# Soil_EH_Comparator.net
KiCad netlist of a schematic drawn in Altium Designer
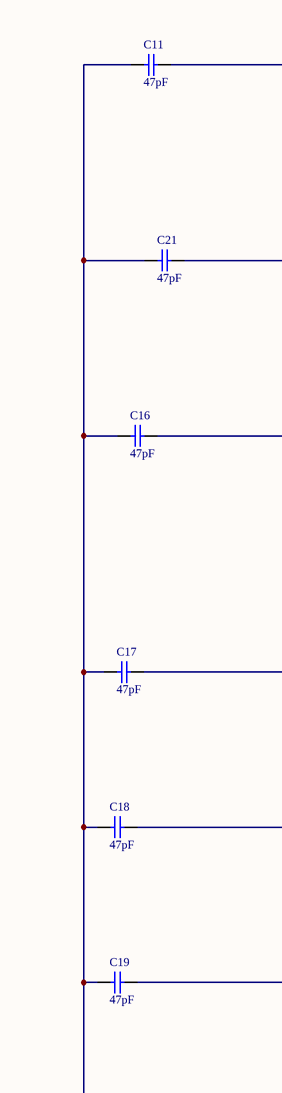
[diagram p0: Soil_EH_Comparator.SchDoc, top left]
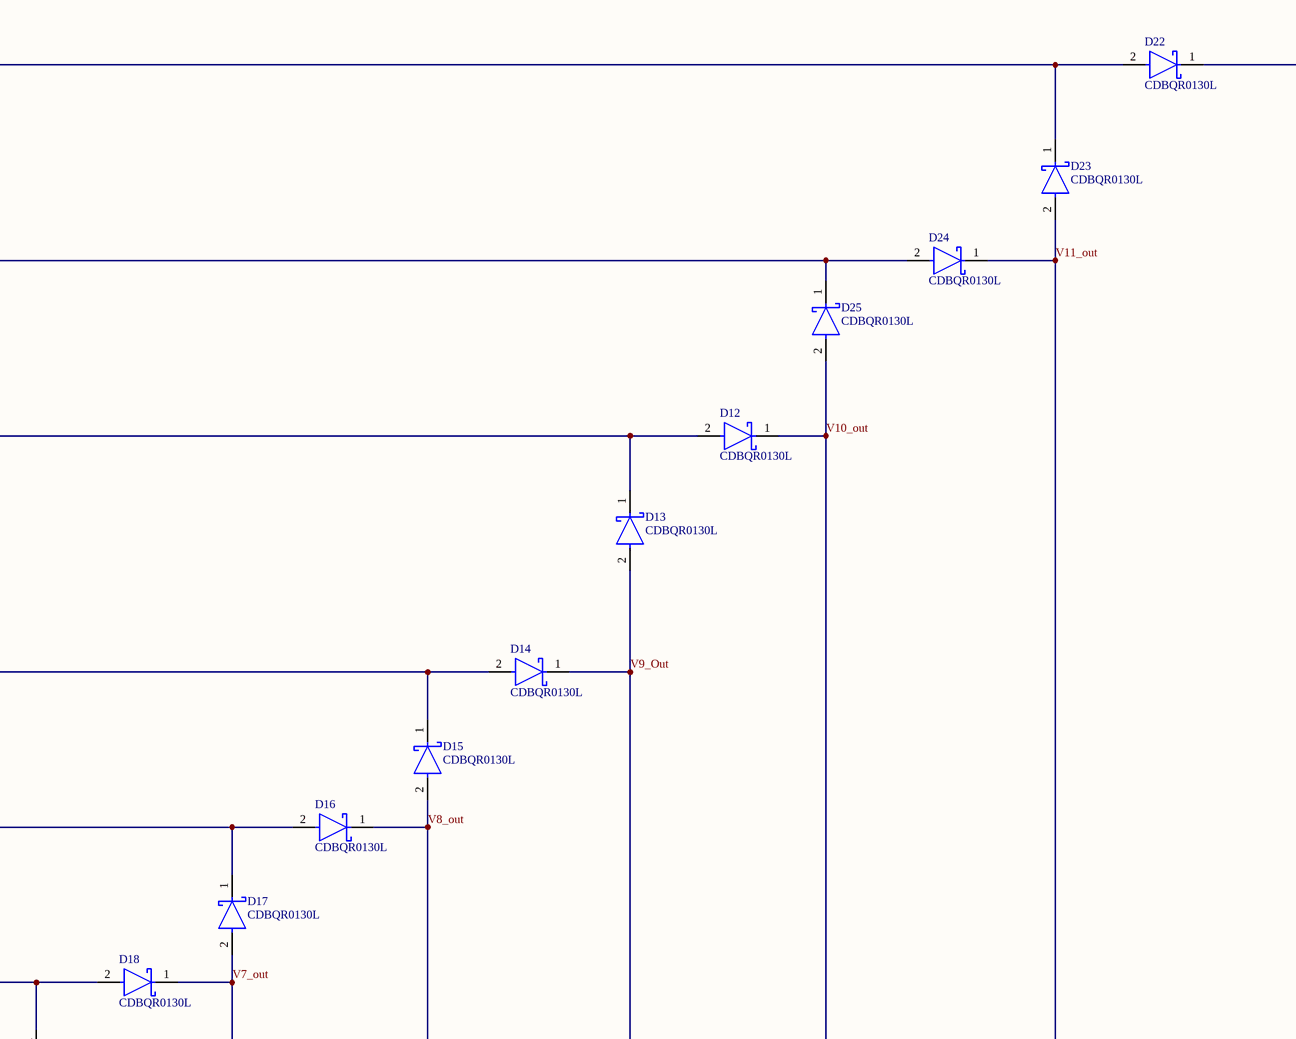
[diagram p1: Soil_EH_Comparator.SchDoc, top middle]
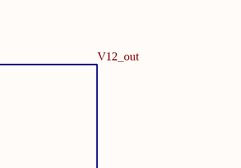
[diagram p2: Soil_EH_Comparator.SchDoc, top right]
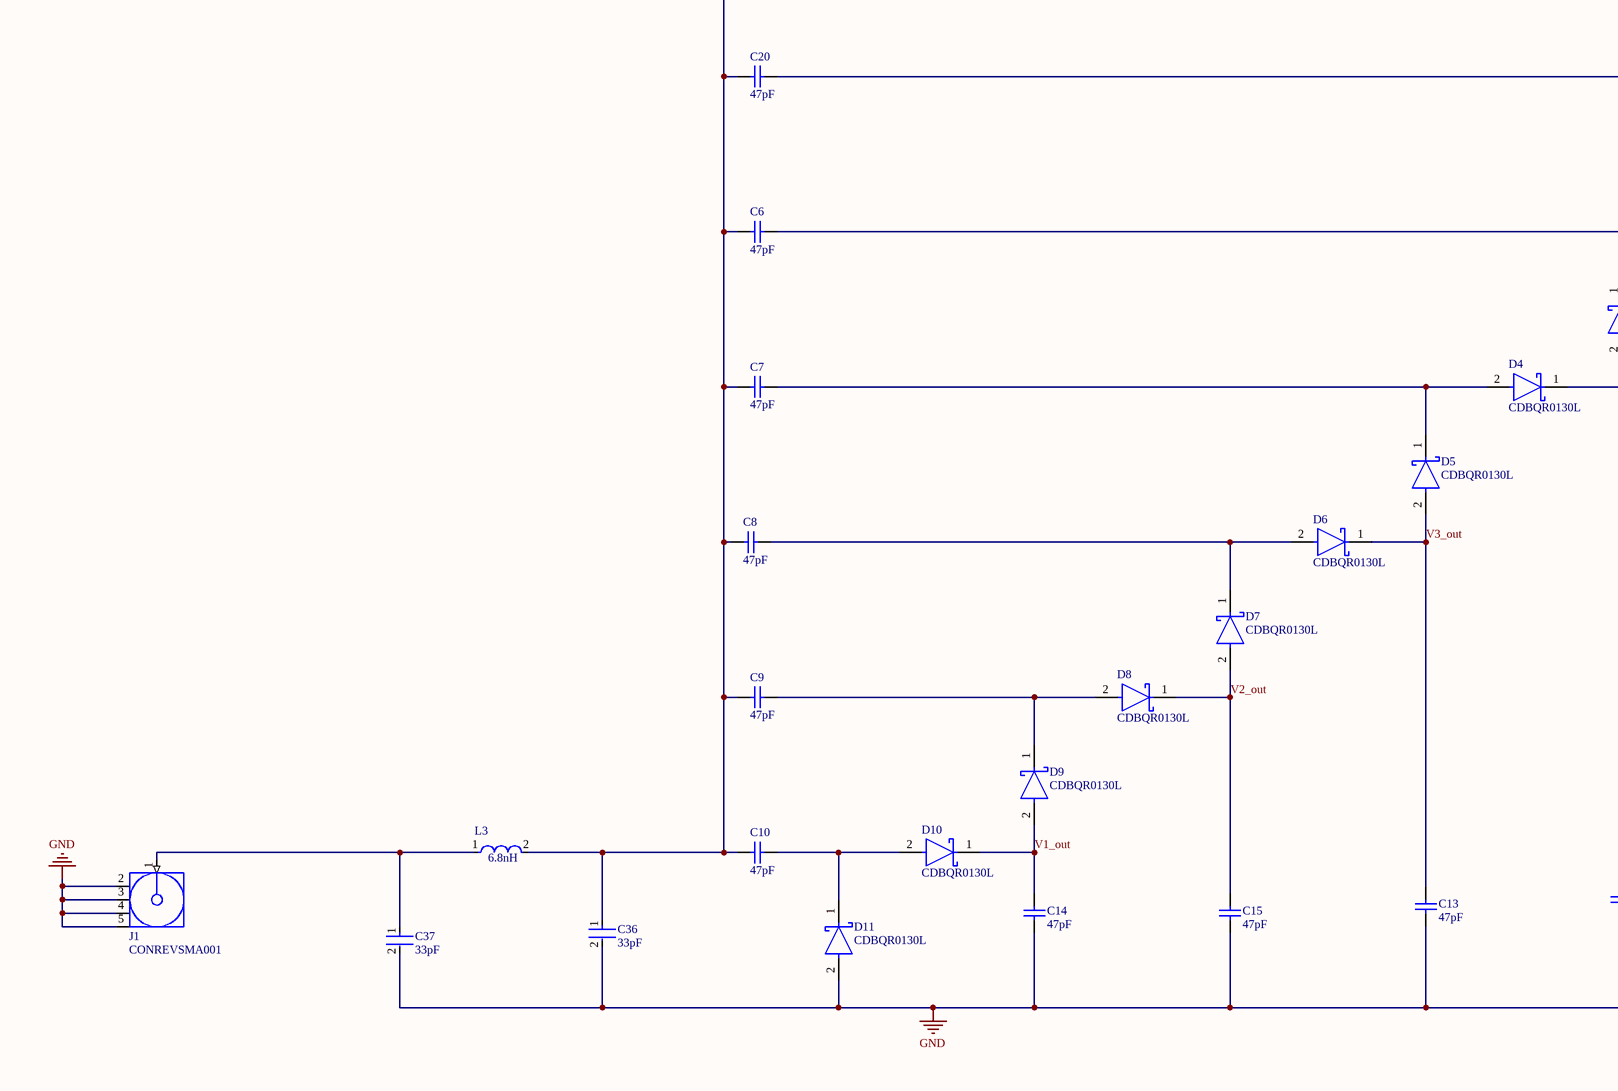
[diagram p3: Soil_EH_Comparator.SchDoc, bottom left]
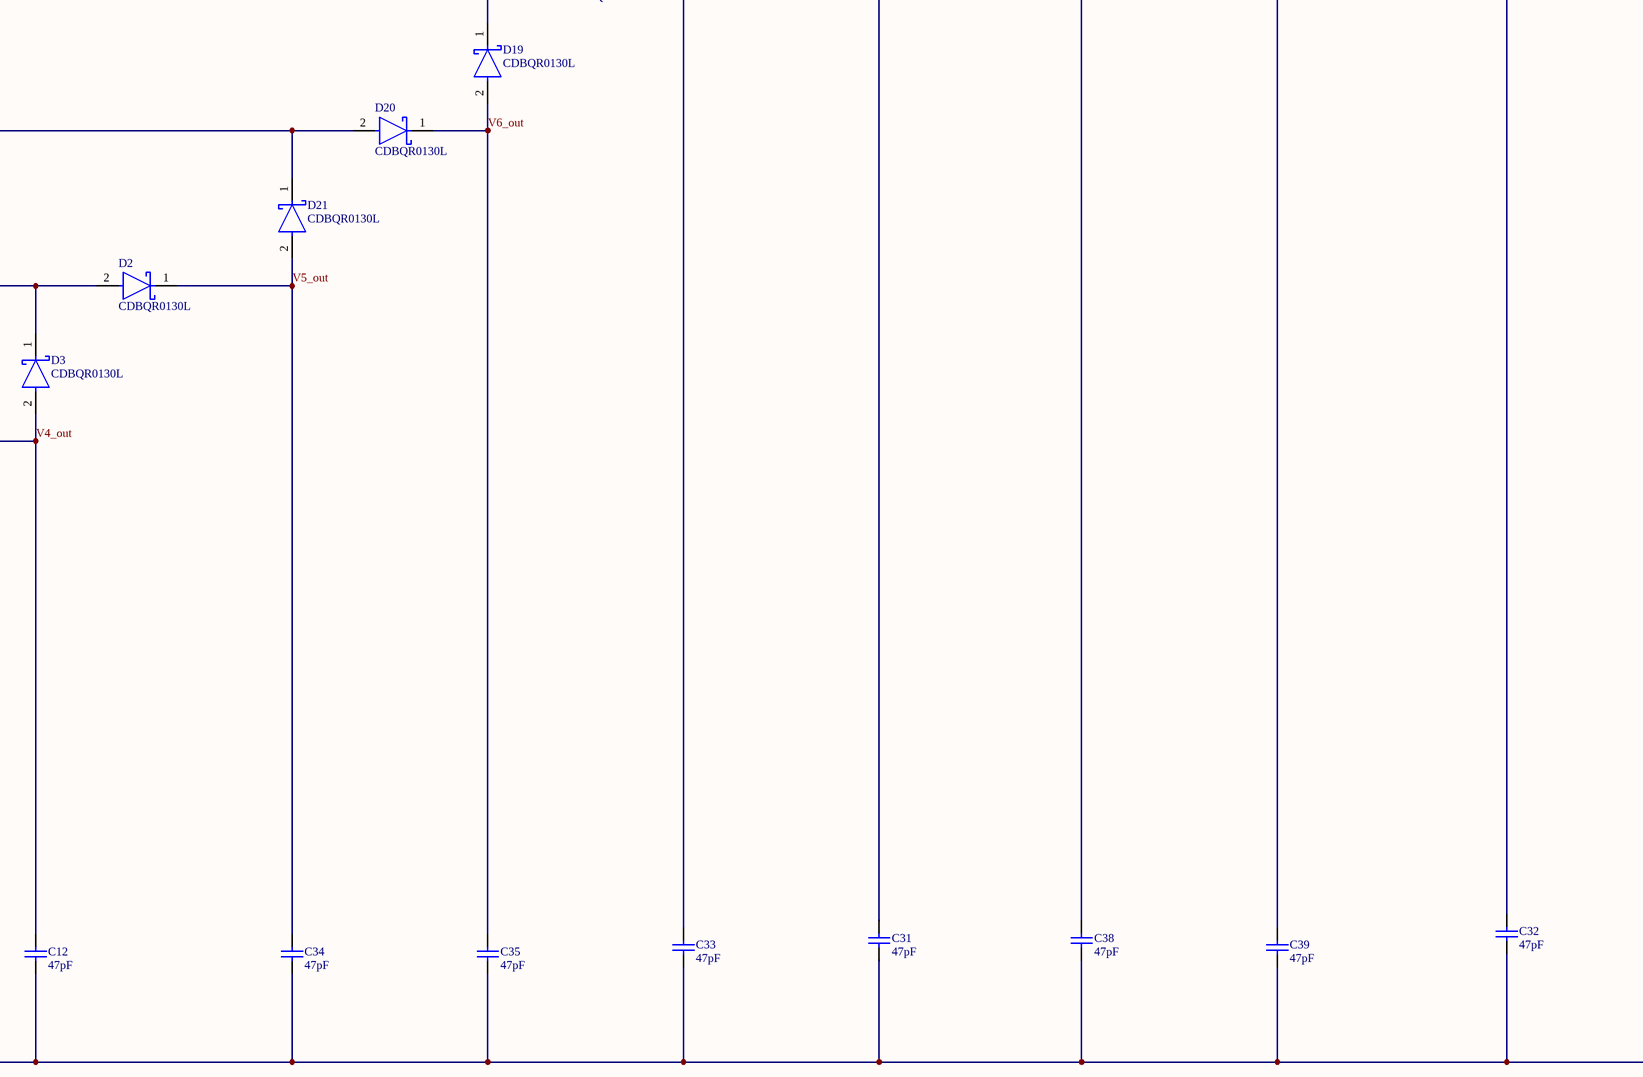
[diagram p4: Soil_EH_Comparator.SchDoc, bottom middle]
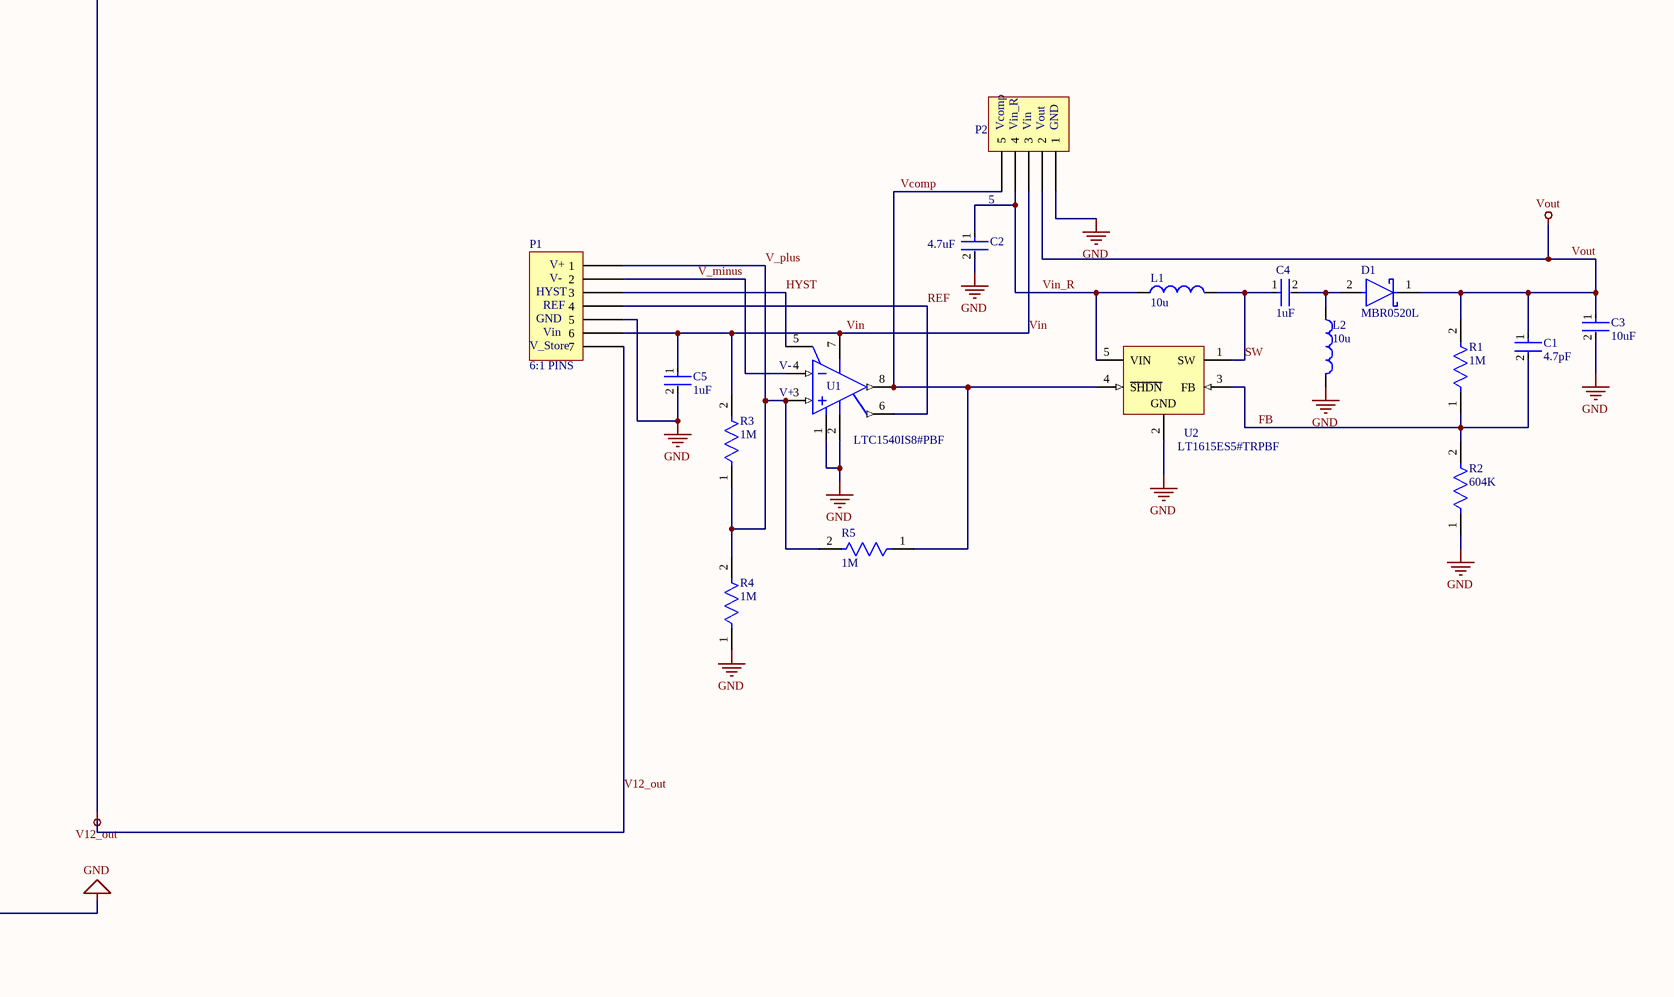
[diagram p5: Soil_EH_Comparator.SchDoc, bottom right]

(export (version "E")
  (design (tool "Eeschema 10.0.6"))
  (components
    (comp (ref "C1")
      (value "4.7pF")
      (footprint "FP-C0603C-CF-MFG")
      (description "CAP CER 4.7PF 25V C0G/NP0 0603")
      (fields
        (field (name "OCTOPART") "https://octopart.com/c0603c479c3gacauto-kemet-21768564")
        (field (name "MANUFACTURER PART NUMBER") "C0603C479C3GACAUTO")
      )
      (libsource (lib "Altium Content Vault") (part "b4654b650e69147ec39a6b967a45e02"))
    )
    (comp (ref "C2")
      (value "4.7uF")
      (footprint "FP-GRM188-0_15-IPC_C")
      (description "Chip Multilayer Ceramic Capacitors for General Purpose, 0603, 4.7uF, X5R, 15%, 10%, 25V")
      (fields (field (name "VOLTAGE") "25V") (field (name "TOLERANCE") "10%"))
      (libsource (lib "Altium Content Vault") (part "02cd4be3c70576c341d710602a673aa"))
    )
    (comp (ref "C3")
      (value "10uF")
      (footprint "FP-GRM21B-0_1-MFG")
      (description "Chip Multilayer Ceramic Capacitors for General Purpose, 0805, 10uF, X5R, 15%, 10%, 16V")
      (fields (field (name "TOLERANCE") "10%") (field (name "VOLTAGE") "16V"))
      (libsource (lib "Altium Content Vault") (part "b4654b650e69147ec39a6b967a45e02"))
    )
    (comp (ref "C4")
      (value "1uF")
      (footprint "FP-0603-L_1_6_0_1-W_0_8_0-IPC_C")
      (description "None")
      (fields (field (name "TOLERANCE") "10%"))
      (libsource (lib "Altium Content Vault") (part "02cd4be3c70576c341d710602a673aa"))
    )
    (comp (ref "C5")
      (value "1uF")
      (footprint "FP-0603-L_1_6_0_1-W_0_8_0-IPC_C")
      (description "None")
      (fields (field (name "TOLERANCE") "10%"))
      (libsource (lib "Altium Content Vault") (part "02cd4be3c70576c341d710602a673aa"))
    )
    (comp (ref "C6")
      (value "47pF")
      (footprint "CAPC1608X95X40LL15T15")
      (fields (field (name "PART NUMBER") "VJ0603A470FXACW1BC") (field (name "MANUFACTURER") "Vitramon"))
      (libsource (lib "Altium Content Vault") (part "CAP"))
    )
    (comp (ref "C7")
      (value "47pF")
      (footprint "CAPC1608X95X40LL15T15")
      (fields (field (name "PART NUMBER") "VJ0603A470FXACW1BC") (field (name "MANUFACTURER") "Vitramon"))
      (libsource (lib "Altium Content Vault") (part "CAP"))
    )
    (comp (ref "C8")
      (value "47pF")
      (footprint "CAPC1608X95X40LL15T15")
      (fields (field (name "PART NUMBER") "VJ0603A470FXACW1BC") (field (name "MANUFACTURER") "Vitramon"))
      (libsource (lib "Altium Content Vault") (part "CAP"))
    )
    (comp (ref "C9")
      (value "47pF")
      (footprint "CAPC1608X95X40LL15T15")
      (fields (field (name "PART NUMBER") "VJ0603A470FXACW1BC") (field (name "MANUFACTURER") "Vitramon"))
      (libsource (lib "Altium Content Vault") (part "CAP"))
    )
    (comp (ref "C10")
      (value "47pF")
      (footprint "CAPC1608X95X40LL15T15")
      (fields (field (name "PART NUMBER") "VJ0603A470FXACW1BC") (field (name "MANUFACTURER") "Vitramon"))
      (libsource (lib "Altium Content Vault") (part "CAP"))
    )
    (comp (ref "C11")
      (value "47pF")
      (footprint "CAPC1608X95X40LL15T15")
      (fields (field (name "PART NUMBER") "VJ0603A470FXACW1BC") (field (name "MANUFACTURER") "Vitramon"))
      (libsource (lib "Altium Content Vault") (part "CAP"))
    )
    (comp (ref "C12")
      (value "47pF")
      (footprint "CAPC1608X95X40LL15T15")
      (fields (field (name "PART NUMBER") "VJ0603A470FXACW1BC") (field (name "MANUFACTURER") "Vitramon"))
      (libsource (lib "Altium Content Vault") (part "CAP"))
    )
    (comp (ref "C13")
      (value "47pF")
      (footprint "CAPC1608X95X40LL15T15")
      (fields (field (name "PART NUMBER") "VJ0603A470FXACW1BC") (field (name "MANUFACTURER") "Vitramon"))
      (libsource (lib "Altium Content Vault") (part "CAP"))
    )
    (comp (ref "C14")
      (value "47pF")
      (footprint "CAPC1608X95X40LL15T15")
      (fields (field (name "PART NUMBER") "VJ0603A470FXACW1BC") (field (name "MANUFACTURER") "Vitramon"))
      (libsource (lib "Altium Content Vault") (part "CAP"))
    )
    (comp (ref "C15")
      (value "47pF")
      (footprint "CAPC1608X95X40LL15T15")
      (fields (field (name "PART NUMBER") "VJ0603A470FXACW1BC") (field (name "MANUFACTURER") "Vitramon"))
      (libsource (lib "Altium Content Vault") (part "CAP"))
    )
    (comp (ref "C16")
      (value "47pF")
      (footprint "CAPC1608X95X40LL15T15")
      (fields (field (name "PART NUMBER") "VJ0603A470FXACW1BC") (field (name "MANUFACTURER") "Vitramon"))
      (libsource (lib "Altium Content Vault") (part "CAP"))
    )
    (comp (ref "C17")
      (value "47pF")
      (footprint "CAPC1608X95X40LL15T15")
      (fields (field (name "PART NUMBER") "VJ0603A470FXACW1BC") (field (name "MANUFACTURER") "Vitramon"))
      (libsource (lib "Altium Content Vault") (part "CAP"))
    )
    (comp (ref "C18")
      (value "47pF")
      (footprint "CAPC1608X95X40LL15T15")
      (fields (field (name "PART NUMBER") "VJ0603A470FXACW1BC") (field (name "MANUFACTURER") "Vitramon"))
      (libsource (lib "Altium Content Vault") (part "CAP"))
    )
    (comp (ref "C19")
      (value "47pF")
      (footprint "CAPC1608X95X40LL15T15")
      (fields (field (name "PART NUMBER") "VJ0603A470FXACW1BC") (field (name "MANUFACTURER") "Vitramon"))
      (libsource (lib "Altium Content Vault") (part "CAP"))
    )
    (comp (ref "C20")
      (value "47pF")
      (footprint "CAPC1608X95X40LL15T15")
      (fields (field (name "PART NUMBER") "VJ0603A470FXACW1BC") (field (name "MANUFACTURER") "Vitramon"))
      (libsource (lib "Altium Content Vault") (part "CAP"))
    )
    (comp (ref "C21")
      (value "47pF")
      (footprint "CAPC1608X95X40LL15T15")
      (fields (field (name "PART NUMBER") "VJ0603A470FXACW1BC") (field (name "MANUFACTURER") "Vitramon"))
      (libsource (lib "Altium Content Vault") (part "CAP"))
    )
    (comp (ref "C31")
      (value "47pF")
      (footprint "CAPC1608X95X40LL15T15")
      (fields (field (name "PART NUMBER") "VJ0603A470FXACW1BC") (field (name "MANUFACTURER") "Vitramon"))
      (libsource (lib "Altium Content Vault") (part "CAP"))
    )
    (comp (ref "C32")
      (value "47pF")
      (footprint "CAPC1608X95X40LL15T15")
      (fields (field (name "PART NUMBER") "VJ0603A470FXACW1BC") (field (name "MANUFACTURER") "Vitramon"))
      (libsource (lib "Altium Content Vault") (part "CAP"))
    )
    (comp (ref "C33")
      (value "47pF")
      (footprint "CAPC1608X95X40LL15T15")
      (fields (field (name "PART NUMBER") "VJ0603A470FXACW1BC") (field (name "MANUFACTURER") "Vitramon"))
      (libsource (lib "Altium Content Vault") (part "CAP"))
    )
    (comp (ref "C34")
      (value "47pF")
      (footprint "CAPC1608X95X40LL15T15")
      (fields (field (name "PART NUMBER") "VJ0603A470FXACW1BC") (field (name "MANUFACTURER") "Vitramon"))
      (libsource (lib "Altium Content Vault") (part "CAP"))
    )
    (comp (ref "C35")
      (value "47pF")
      (footprint "CAPC1608X95X40LL15T15")
      (fields (field (name "PART NUMBER") "VJ0603A470FXACW1BC") (field (name "MANUFACTURER") "Vitramon"))
      (libsource (lib "Altium Content Vault") (part "CAP"))
    )
    (comp (ref "C36")
      (value "33pF")
      (footprint "FP-C0603C-CF-MFG")
      (description "CAP CER 33PF 50V 1% NP0 0603")
      (fields
        (field (name "OCTOPART") "https://octopart.com/c0603c330f5gactu-kemet-9143758")
        (field (name "TOLERANCE") "0.01")
      )
      (libsource (lib "Altium Content Vault") (part "b4654b650e69147ec39a6b967a45e02"))
    )
    (comp (ref "C37")
      (value "33pF")
      (footprint "FP-C0603C-CF-MFG")
      (description "CAP CER 33PF 50V 1% NP0 0603")
      (fields
        (field (name "OCTOPART") "https://octopart.com/c0603c330f5gactu-kemet-9143758")
        (field (name "TOLERANCE") "0.01")
      )
      (libsource (lib "Altium Content Vault") (part "b4654b650e69147ec39a6b967a45e02"))
    )
    (comp (ref "C38")
      (value "47pF")
      (footprint "CAPC1608X95X40LL15T15")
      (fields (field (name "PART NUMBER") "VJ0603A470FXACW1BC") (field (name "MANUFACTURER") "Vitramon"))
      (libsource (lib "Altium Content Vault") (part "CAP"))
    )
    (comp (ref "C39")
      (value "47pF")
      (footprint "CAPC1608X95X40LL15T15")
      (fields (field (name "PART NUMBER") "VJ0603A470FXACW1BC") (field (name "MANUFACTURER") "Vitramon"))
      (libsource (lib "Altium Content Vault") (part "CAP"))
    )
    (comp (ref "D1")
      (value "MBR0520L")
      (footprint "FP-MA02A-MFG")
      (description "DIODE SCHOTTKY 20V 500MA SOD123")
      (libsource (lib "Altium Content Vault") (part "1d6ec82d83fb6aee721767c19dac4b9"))
    )
    (comp (ref "D2")
      (value "CDBQR0130L")
      (footprint "FP-0402-SOD-923F-MFG")
      (description "DIODE SCHOTTKY 30V 100MA 0402")
      (libsource (lib "Altium Content Vault") (part "1d6ec82d83fb6aee721767c19dac4b9"))
    )
    (comp (ref "D3")
      (value "CDBQR0130L")
      (footprint "FP-0402-SOD-923F-MFG")
      (description "DIODE SCHOTTKY 30V 100MA 0402")
      (libsource (lib "Altium Content Vault") (part "1d6ec82d83fb6aee721767c19dac4b9"))
    )
    (comp (ref "D4")
      (value "CDBQR0130L")
      (footprint "FP-0402-SOD-923F-MFG")
      (description "DIODE SCHOTTKY 30V 100MA 0402")
      (libsource (lib "Altium Content Vault") (part "1d6ec82d83fb6aee721767c19dac4b9"))
    )
    (comp (ref "D5")
      (value "CDBQR0130L")
      (footprint "FP-0402-SOD-923F-MFG")
      (description "DIODE SCHOTTKY 30V 100MA 0402")
      (libsource (lib "Altium Content Vault") (part "1d6ec82d83fb6aee721767c19dac4b9"))
    )
    (comp (ref "D6")
      (value "CDBQR0130L")
      (footprint "FP-0402-SOD-923F-MFG")
      (description "DIODE SCHOTTKY 30V 100MA 0402")
      (libsource (lib "Altium Content Vault") (part "1d6ec82d83fb6aee721767c19dac4b9"))
    )
    (comp (ref "D7")
      (value "CDBQR0130L")
      (footprint "FP-0402-SOD-923F-MFG")
      (description "DIODE SCHOTTKY 30V 100MA 0402")
      (libsource (lib "Altium Content Vault") (part "1d6ec82d83fb6aee721767c19dac4b9"))
    )
    (comp (ref "D8")
      (value "CDBQR0130L")
      (footprint "FP-0402-SOD-923F-MFG")
      (description "DIODE SCHOTTKY 30V 100MA 0402")
      (libsource (lib "Altium Content Vault") (part "1d6ec82d83fb6aee721767c19dac4b9"))
    )
    (comp (ref "D9")
      (value "CDBQR0130L")
      (footprint "FP-0402-SOD-923F-MFG")
      (description "DIODE SCHOTTKY 30V 100MA 0402")
      (libsource (lib "Altium Content Vault") (part "1d6ec82d83fb6aee721767c19dac4b9"))
    )
    (comp (ref "D10")
      (value "CDBQR0130L")
      (footprint "FP-0402-SOD-923F-MFG")
      (description "DIODE SCHOTTKY 30V 100MA 0402")
      (libsource (lib "Altium Content Vault") (part "1d6ec82d83fb6aee721767c19dac4b9"))
    )
    (comp (ref "D11")
      (value "CDBQR0130L")
      (footprint "FP-0402-SOD-923F-MFG")
      (description "DIODE SCHOTTKY 30V 100MA 0402")
      (libsource (lib "Altium Content Vault") (part "1d6ec82d83fb6aee721767c19dac4b9"))
    )
    (comp (ref "D12")
      (value "CDBQR0130L")
      (footprint "FP-0402-SOD-923F-MFG")
      (description "DIODE SCHOTTKY 30V 100MA 0402")
      (libsource (lib "Altium Content Vault") (part "1d6ec82d83fb6aee721767c19dac4b9"))
    )
    (comp (ref "D13")
      (value "CDBQR0130L")
      (footprint "FP-0402-SOD-923F-MFG")
      (description "DIODE SCHOTTKY 30V 100MA 0402")
      (libsource (lib "Altium Content Vault") (part "1d6ec82d83fb6aee721767c19dac4b9"))
    )
    (comp (ref "D14")
      (value "CDBQR0130L")
      (footprint "FP-0402-SOD-923F-MFG")
      (description "DIODE SCHOTTKY 30V 100MA 0402")
      (libsource (lib "Altium Content Vault") (part "1d6ec82d83fb6aee721767c19dac4b9"))
    )
    (comp (ref "D15")
      (value "CDBQR0130L")
      (footprint "FP-0402-SOD-923F-MFG")
      (description "DIODE SCHOTTKY 30V 100MA 0402")
      (libsource (lib "Altium Content Vault") (part "1d6ec82d83fb6aee721767c19dac4b9"))
    )
    (comp (ref "D16")
      (value "CDBQR0130L")
      (footprint "FP-0402-SOD-923F-MFG")
      (description "DIODE SCHOTTKY 30V 100MA 0402")
      (libsource (lib "Altium Content Vault") (part "1d6ec82d83fb6aee721767c19dac4b9"))
    )
    (comp (ref "D17")
      (value "CDBQR0130L")
      (footprint "FP-0402-SOD-923F-MFG")
      (description "DIODE SCHOTTKY 30V 100MA 0402")
      (libsource (lib "Altium Content Vault") (part "1d6ec82d83fb6aee721767c19dac4b9"))
    )
    (comp (ref "D18")
      (value "CDBQR0130L")
      (footprint "FP-0402-SOD-923F-MFG")
      (description "DIODE SCHOTTKY 30V 100MA 0402")
      (libsource (lib "Altium Content Vault") (part "1d6ec82d83fb6aee721767c19dac4b9"))
    )
    (comp (ref "D19")
      (value "CDBQR0130L")
      (footprint "FP-0402-SOD-923F-MFG")
      (description "DIODE SCHOTTKY 30V 100MA 0402")
      (libsource (lib "Altium Content Vault") (part "1d6ec82d83fb6aee721767c19dac4b9"))
    )
    (comp (ref "D20")
      (value "CDBQR0130L")
      (footprint "FP-0402-SOD-923F-MFG")
      (description "DIODE SCHOTTKY 30V 100MA 0402")
      (libsource (lib "Altium Content Vault") (part "1d6ec82d83fb6aee721767c19dac4b9"))
    )
    (comp (ref "D21")
      (value "CDBQR0130L")
      (footprint "FP-0402-SOD-923F-MFG")
      (description "DIODE SCHOTTKY 30V 100MA 0402")
      (libsource (lib "Altium Content Vault") (part "1d6ec82d83fb6aee721767c19dac4b9"))
    )
    (comp (ref "D22")
      (value "CDBQR0130L")
      (footprint "FP-0402-SOD-923F-MFG")
      (description "DIODE SCHOTTKY 30V 100MA 0402")
      (libsource (lib "Altium Content Vault") (part "1d6ec82d83fb6aee721767c19dac4b9"))
    )
    (comp (ref "D23")
      (value "CDBQR0130L")
      (footprint "FP-0402-SOD-923F-MFG")
      (description "DIODE SCHOTTKY 30V 100MA 0402")
      (libsource (lib "Altium Content Vault") (part "1d6ec82d83fb6aee721767c19dac4b9"))
    )
    (comp (ref "D24")
      (value "CDBQR0130L")
      (footprint "FP-0402-SOD-923F-MFG")
      (description "DIODE SCHOTTKY 30V 100MA 0402")
      (libsource (lib "Altium Content Vault") (part "1d6ec82d83fb6aee721767c19dac4b9"))
    )
    (comp (ref "D25")
      (value "CDBQR0130L")
      (footprint "FP-0402-SOD-923F-MFG")
      (description "DIODE SCHOTTKY 30V 100MA 0402")
      (libsource (lib "Altium Content Vault") (part "1d6ec82d83fb6aee721767c19dac4b9"))
    )
    (comp (ref "J1")
      (value "CONREVSMA001")
      (footprint "CON-REVSMA")
      (description "RP-SMA Female PCB Mount Connector, Thru-Hole")
      (libsource (lib "Altium Content Vault") (part "CN-1P-F-RF5"))
    )
    (comp (ref "L1")
      (value "10u")
      (footprint "Inductor_Footprint:IND_LQH43CN100K03L")
      (description "Inductor")
      (libsource (lib "Simulation Generic Components") (part "Inductor"))
    )
    (comp (ref "L2")
      (value "10u")
      (footprint "Inductor_Footprint:IND_LQH43CN100K03L")
      (description "Inductor")
      (libsource (lib "Simulation Generic Components") (part "Inductor"))
    )
    (comp (ref "L3")
      (value "6.8nH")
      (footprint "FP-LQW18AN_00-MFG")
      (description "Wire Wound RF Inductor 6.8nH ±0.5nH 750mA 0.082Ω 0603 (1608)")
      (libsource (lib "Altium Content Vault") (part "725321dda6339637d4d059423bc1c3c"))
    )
    (comp (ref "P1")
      (value "6:1 PINS")
      (footprint "PcbLib1:6:1 pins")
      (libsource (lib "Schlib1") (part "6{colon}1 PINS"))
    )
    (comp (ref "P2") (value "5") (footprint "5") (libsource (lib "Schlib1") (part "5")))
    (comp (ref "R1")
      (value "1M")
      (footprint "FP-ERJ3EK-IPC_C")
      (description "RES SMD 1M OHM 1% 1/10W 0603")
      (fields (field (name "TOLERANCE") "1%"))
      (libsource (lib "Altium Content Vault") (part "1029c3af85768c4190bb7ad29bc67b5"))
    )
    (comp (ref "R2")
      (value "604K")
      (footprint "FP-RMCF0603-IPC_B")
      (description "604kΩ ±1% 0.1W 0603 Thick Film Chip Resistor AEC-Q200 compliant")
      (fields (field (name "TOLERANCE") "1%"))
      (libsource (lib "Altium Content Vault") (part "1029c3af85768c4190bb7ad29bc67b5"))
    )
    (comp (ref "R3")
      (value "1M")
      (footprint "FP-ERJ3EK-IPC_C")
      (description "RES SMD 1M OHM 1% 1/10W 0603")
      (fields (field (name "TOLERANCE") "1%"))
      (libsource (lib "Altium Content Vault") (part "1029c3af85768c4190bb7ad29bc67b5"))
    )
    (comp (ref "R4")
      (value "1M")
      (footprint "FP-ERJ3EK-IPC_C")
      (description "RES SMD 1M OHM 1% 1/10W 0603")
      (fields (field (name "TOLERANCE") "1%"))
      (libsource (lib "Altium Content Vault") (part "1029c3af85768c4190bb7ad29bc67b5"))
    )
    (comp (ref "R5")
      (value "1M")
      (footprint "FP-ERJ3EK-IPC_C")
      (description "RES SMD 1M OHM 1% 1/10W 0603")
      (fields (field (name "TOLERANCE") "1%"))
      (libsource (lib "Altium Content Vault") (part "1029c3af85768c4190bb7ad29bc67b5"))
    )
    (comp (ref "U1")
      (value "LTC1540IS8#PBF")
      (footprint "LT-S8_L")
      (description "Nanopower Comparator with Reference, 1 Channel, 2 to 11 V, -40 to +85 degC, 8-pin SOP (S8)")
      (fields
        (field (name "GENERIC PART NUMBER") "LTC1540")
        (field (name "MANUFACTURER") "Linear Technology")
      )
      (libsource (lib "Altium Content Vault") (part "LT-AN-COMP-2"))
    )
    (comp (ref "U2")
      (value "LT1615ES5#TRPBF")
      (footprint "LT-S5-5-TSOT-23_N")
      (description "Micropower Step-Up DC/DC Converter, 5-pin SOT23 (S5-5), -40 to 85 degC, Pb-Free, Tape and Reel")
      (fields (field (name "MANUFACTURER") "Linear Technology"))
      (libsource (lib "Altium Content Vault") (part "LT-LT161XXX_193XX_3460-S5-5"))
    )
  )
  (nets
    (net (code "1") (name "/FB") (class "Default")
      (node (ref "C1") (pin "2") (pinfunction "2_2") (pintype "passive"))
      (node (ref "R1") (pin "1") (pinfunction "1_1") (pintype "passive"))
      (node (ref "R2") (pin "2") (pinfunction "2_2") (pintype "passive"))
      (node (ref "U2") (pin "3") (pinfunction "FB_3") (pintype "input"))
    )
    (net (code "2") (name "/HYST") (class "Default")
      (node (ref "P1") (pin "3") (pinfunction "3_3") (pintype "passive"))
      (node (ref "U1") (pin "5") (pinfunction "HYST_5") (pintype "passive"))
    )
    (net (code "3") (name "/REF") (class "Default")
      (node (ref "P1") (pin "4") (pinfunction "4_4") (pintype "passive"))
      (node (ref "U1") (pin "6") (pinfunction "REF_6") (pintype "output"))
    )
    (net (code "4") (name "/SW") (class "Default")
      (node (ref "C4") (pin "1") (pinfunction "1_1") (pintype "passive"))
      (node (ref "L1") (pin "2") (pinfunction "2_2") (pintype "passive"))
      (node (ref "U2") (pin "1") (pinfunction "SW_1") (pintype "power_in"))
    )
    (net (code "5") (name "/V1_out") (class "Default")
      (node (ref "C14") (pin "2") (pinfunction "2_2") (pintype "passive"))
      (node (ref "D10") (pin "1") (pinfunction "C_1") (pintype "passive"))
      (node (ref "D9") (pin "2") (pinfunction "A_2") (pintype "passive"))
    )
    (net (code "6") (name "/V2_out") (class "Default")
      (node (ref "C15") (pin "2") (pinfunction "2_2") (pintype "passive"))
      (node (ref "D7") (pin "2") (pinfunction "A_2") (pintype "passive"))
      (node (ref "D8") (pin "1") (pinfunction "C_1") (pintype "passive"))
    )
    (net (code "7") (name "/V3_out") (class "Default")
      (node (ref "C13") (pin "2") (pinfunction "2_2") (pintype "passive"))
      (node (ref "D5") (pin "2") (pinfunction "A_2") (pintype "passive"))
      (node (ref "D6") (pin "1") (pinfunction "C_1") (pintype "passive"))
    )
    (net (code "8") (name "/V4_out") (class "Default")
      (node (ref "C12") (pin "2") (pinfunction "2_2") (pintype "passive"))
      (node (ref "D3") (pin "2") (pinfunction "A_2") (pintype "passive"))
      (node (ref "D4") (pin "1") (pinfunction "C_1") (pintype "passive"))
    )
    (net (code "9") (name "/V5_out") (class "Default")
      (node (ref "C34") (pin "2") (pinfunction "2_2") (pintype "passive"))
      (node (ref "D2") (pin "1") (pinfunction "C_1") (pintype "passive"))
      (node (ref "D21") (pin "2") (pinfunction "A_2") (pintype "passive"))
    )
    (net (code "10") (name "/V6_out") (class "Default")
      (node (ref "C35") (pin "2") (pinfunction "2_2") (pintype "passive"))
      (node (ref "D19") (pin "2") (pinfunction "A_2") (pintype "passive"))
      (node (ref "D20") (pin "1") (pinfunction "C_1") (pintype "passive"))
    )
    (net (code "11") (name "/V7_out") (class "Default")
      (node (ref "C33") (pin "2") (pinfunction "2_2") (pintype "passive"))
      (node (ref "D17") (pin "2") (pinfunction "A_2") (pintype "passive"))
      (node (ref "D18") (pin "1") (pinfunction "C_1") (pintype "passive"))
    )
    (net (code "12") (name "/V8_out") (class "Default")
      (node (ref "C31") (pin "2") (pinfunction "2_2") (pintype "passive"))
      (node (ref "D15") (pin "2") (pinfunction "A_2") (pintype "passive"))
      (node (ref "D16") (pin "1") (pinfunction "C_1") (pintype "passive"))
    )
    (net (code "13") (name "/V9_Out") (class "Default")
      (node (ref "C38") (pin "2") (pinfunction "2_2") (pintype "passive"))
      (node (ref "D13") (pin "2") (pinfunction "A_2") (pintype "passive"))
      (node (ref "D14") (pin "1") (pinfunction "C_1") (pintype "passive"))
    )
    (net (code "14") (name "/V10_out") (class "Default")
      (node (ref "C39") (pin "2") (pinfunction "2_2") (pintype "passive"))
      (node (ref "D12") (pin "1") (pinfunction "C_1") (pintype "passive"))
      (node (ref "D25") (pin "2") (pinfunction "A_2") (pintype "passive"))
    )
    (net (code "15") (name "/V11_out") (class "Default")
      (node (ref "C32") (pin "2") (pinfunction "2_2") (pintype "passive"))
      (node (ref "D23") (pin "2") (pinfunction "A_2") (pintype "passive"))
      (node (ref "D24") (pin "1") (pinfunction "C_1") (pintype "passive"))
    )
    (net (code "16") (name "/V_minus") (class "Default")
      (node (ref "P1") (pin "2") (pinfunction "2_2") (pintype "passive"))
      (node (ref "U1") (pin "4") (pinfunction "IN-_4") (pintype "input"))
    )
    (net (code "17") (name "/V_plus") (class "Default")
      (node (ref "P1") (pin "1") (pinfunction "1_1") (pintype "passive"))
      (node (ref "R3") (pin "1") (pinfunction "1_1") (pintype "passive"))
      (node (ref "R4") (pin "2") (pinfunction "2_2") (pintype "passive"))
      (node (ref "R5") (pin "2") (pinfunction "2_2") (pintype "passive"))
      (node (ref "U1") (pin "3") (pinfunction "IN+_3") (pintype "input"))
    )
    (net (code "18") (name "/Vcomp") (class "Default")
      (node (ref "P2") (pin "5") (pinfunction "5_5") (pintype "passive"))
      (node (ref "R5") (pin "1") (pinfunction "1_1") (pintype "passive"))
      (node (ref "U1") (pin "8") (pinfunction "OUT_8") (pintype "output"))
      (node (ref "U2") (pin "4") (pinfunction "~{SHDN}_4") (pintype "input"))
    )
    (net (code "19") (name "/Vin") (class "Default")
      (node (ref "C5") (pin "1") (pinfunction "1_1") (pintype "passive"))
      (node (ref "P1") (pin "6") (pinfunction "6_6") (pintype "passive"))
      (node (ref "P2") (pin "3") (pinfunction "3_3") (pintype "passive"))
      (node (ref "R3") (pin "2") (pinfunction "2_2") (pintype "passive"))
      (node (ref "U1") (pin "7") (pinfunction "V+_7") (pintype "power_in"))
    )
    (net (code "20") (name "/Vin_R") (class "Default")
      (node (ref "C2") (pin "1") (pinfunction "1_1") (pintype "passive"))
      (node (ref "L1") (pin "1") (pinfunction "1_1") (pintype "passive"))
      (node (ref "P2") (pin "4") (pinfunction "4_4") (pintype "passive"))
      (node (ref "U2") (pin "5") (pinfunction "VIN_5") (pintype "power_in"))
    )
    (net (code "21") (name "GND") (class "Default")
      (node (ref "C12") (pin "1") (pinfunction "1_1") (pintype "passive"))
      (node (ref "C13") (pin "1") (pinfunction "1_1") (pintype "passive"))
      (node (ref "C14") (pin "1") (pinfunction "1_1") (pintype "passive"))
      (node (ref "C15") (pin "1") (pinfunction "1_1") (pintype "passive"))
      (node (ref "C2") (pin "2") (pinfunction "2_2") (pintype "passive"))
      (node (ref "C3") (pin "2") (pinfunction "2_2") (pintype "passive"))
      (node (ref "C31") (pin "1") (pinfunction "1_1") (pintype "passive"))
      (node (ref "C32") (pin "1") (pinfunction "1_1") (pintype "passive"))
      (node (ref "C33") (pin "1") (pinfunction "1_1") (pintype "passive"))
      (node (ref "C34") (pin "1") (pinfunction "1_1") (pintype "passive"))
      (node (ref "C35") (pin "1") (pinfunction "1_1") (pintype "passive"))
      (node (ref "C36") (pin "2") (pinfunction "2_2") (pintype "passive"))
      (node (ref "C37") (pin "2") (pinfunction "2_2") (pintype "passive"))
      (node (ref "C38") (pin "1") (pinfunction "1_1") (pintype "passive"))
      (node (ref "C39") (pin "1") (pinfunction "1_1") (pintype "passive"))
      (node (ref "C5") (pin "2") (pinfunction "2_2") (pintype "passive"))
      (node (ref "D11") (pin "2") (pinfunction "A_2") (pintype "passive"))
      (node (ref "J1") (pin "2") (pinfunction "GND_2") (pintype "power_in"))
      (node (ref "J1") (pin "3") (pinfunction "GND_3") (pintype "power_in"))
      (node (ref "J1") (pin "4") (pinfunction "GND_4") (pintype "power_in"))
      (node (ref "J1") (pin "5") (pinfunction "GND_5") (pintype "power_in"))
      (node (ref "L2") (pin "2") (pinfunction "2_2") (pintype "passive"))
      (node (ref "P1") (pin "5") (pinfunction "5_5") (pintype "passive"))
      (node (ref "P2") (pin "1") (pinfunction "1_1") (pintype "passive"))
      (node (ref "R2") (pin "1") (pinfunction "1_1") (pintype "passive"))
      (node (ref "R4") (pin "1") (pinfunction "1_1") (pintype "passive"))
      (node (ref "U1") (pin "1") (pinfunction "GND_1") (pintype "power_in"))
      (node (ref "U1") (pin "2") (pinfunction "V-_2") (pintype "power_in"))
      (node (ref "U2") (pin "2") (pinfunction "GND_2") (pintype "power_in"))
    )
    (net (code "22") (name "Net-(C10-Pad1)") (class "Default")
      (node (ref "C10") (pin "1") (pinfunction "1_1") (pintype "passive"))
      (node (ref "C11") (pin "1") (pinfunction "1_1") (pintype "passive"))
      (node (ref "C16") (pin "1") (pinfunction "1_1") (pintype "passive"))
      (node (ref "C17") (pin "1") (pinfunction "1_1") (pintype "passive"))
      (node (ref "C18") (pin "1") (pinfunction "1_1") (pintype "passive"))
      (node (ref "C19") (pin "1") (pinfunction "1_1") (pintype "passive"))
      (node (ref "C20") (pin "1") (pinfunction "1_1") (pintype "passive"))
      (node (ref "C21") (pin "1") (pinfunction "1_1") (pintype "passive"))
      (node (ref "C36") (pin "1") (pinfunction "1_1") (pintype "passive"))
      (node (ref "C6") (pin "1") (pinfunction "1_1") (pintype "passive"))
      (node (ref "C7") (pin "1") (pinfunction "1_1") (pintype "passive"))
      (node (ref "C8") (pin "1") (pinfunction "1_1") (pintype "passive"))
      (node (ref "C9") (pin "1") (pinfunction "1_1") (pintype "passive"))
      (node (ref "L3") (pin "2") (pinfunction "2_2") (pintype "passive"))
    )
    (net (code "23") (name "Net-(D1-A)") (class "Default")
      (node (ref "C4") (pin "2") (pinfunction "2_2") (pintype "passive"))
      (node (ref "D1") (pin "2") (pinfunction "A_2") (pintype "passive"))
      (node (ref "L2") (pin "1") (pinfunction "1_1") (pintype "passive"))
    )
    (net (code "24") (name "Net-(D2-A)") (class "Default")
      (node (ref "C6") (pin "2") (pinfunction "2_2") (pintype "passive"))
      (node (ref "D2") (pin "2") (pinfunction "A_2") (pintype "passive"))
      (node (ref "D3") (pin "1") (pinfunction "C_1") (pintype "passive"))
    )
    (net (code "25") (name "Net-(D4-A)") (class "Default")
      (node (ref "C7") (pin "2") (pinfunction "2_2") (pintype "passive"))
      (node (ref "D4") (pin "2") (pinfunction "A_2") (pintype "passive"))
      (node (ref "D5") (pin "1") (pinfunction "C_1") (pintype "passive"))
    )
    (net (code "26") (name "Net-(D6-A)") (class "Default")
      (node (ref "C8") (pin "2") (pinfunction "2_2") (pintype "passive"))
      (node (ref "D6") (pin "2") (pinfunction "A_2") (pintype "passive"))
      (node (ref "D7") (pin "1") (pinfunction "C_1") (pintype "passive"))
    )
    (net (code "27") (name "Net-(D8-A)") (class "Default")
      (node (ref "C9") (pin "2") (pinfunction "2_2") (pintype "passive"))
      (node (ref "D8") (pin "2") (pinfunction "A_2") (pintype "passive"))
      (node (ref "D9") (pin "1") (pinfunction "C_1") (pintype "passive"))
    )
    (net (code "28") (name "Net-(D10-A)") (class "Default")
      (node (ref "C10") (pin "2") (pinfunction "2_2") (pintype "passive"))
      (node (ref "D10") (pin "2") (pinfunction "A_2") (pintype "passive"))
      (node (ref "D11") (pin "1") (pinfunction "C_1") (pintype "passive"))
    )
    (net (code "29") (name "Net-(D12-A)") (class "Default")
      (node (ref "C16") (pin "2") (pinfunction "2_2") (pintype "passive"))
      (node (ref "D12") (pin "2") (pinfunction "A_2") (pintype "passive"))
      (node (ref "D13") (pin "1") (pinfunction "C_1") (pintype "passive"))
    )
    (net (code "30") (name "Net-(D14-A)") (class "Default")
      (node (ref "C17") (pin "2") (pinfunction "2_2") (pintype "passive"))
      (node (ref "D14") (pin "2") (pinfunction "A_2") (pintype "passive"))
      (node (ref "D15") (pin "1") (pinfunction "C_1") (pintype "passive"))
    )
    (net (code "31") (name "Net-(D16-A)") (class "Default")
      (node (ref "C18") (pin "2") (pinfunction "2_2") (pintype "passive"))
      (node (ref "D16") (pin "2") (pinfunction "A_2") (pintype "passive"))
      (node (ref "D17") (pin "1") (pinfunction "C_1") (pintype "passive"))
    )
    (net (code "32") (name "Net-(D18-A)") (class "Default")
      (node (ref "C19") (pin "2") (pinfunction "2_2") (pintype "passive"))
      (node (ref "D18") (pin "2") (pinfunction "A_2") (pintype "passive"))
      (node (ref "D19") (pin "1") (pinfunction "C_1") (pintype "passive"))
    )
    (net (code "33") (name "Net-(D20-A)") (class "Default")
      (node (ref "C20") (pin "2") (pinfunction "2_2") (pintype "passive"))
      (node (ref "D20") (pin "2") (pinfunction "A_2") (pintype "passive"))
      (node (ref "D21") (pin "1") (pinfunction "C_1") (pintype "passive"))
    )
    (net (code "34") (name "Net-(D22-A)") (class "Default")
      (node (ref "C11") (pin "2") (pinfunction "2_2") (pintype "passive"))
      (node (ref "D22") (pin "2") (pinfunction "A_2") (pintype "passive"))
      (node (ref "D23") (pin "1") (pinfunction "C_1") (pintype "passive"))
    )
    (net (code "35") (name "Net-(D24-A)") (class "Default")
      (node (ref "C21") (pin "2") (pinfunction "2_2") (pintype "passive"))
      (node (ref "D24") (pin "2") (pinfunction "A_2") (pintype "passive"))
      (node (ref "D25") (pin "1") (pinfunction "C_1") (pintype "passive"))
    )
    (net (code "36") (name "Net-(J1-Signal)") (class "Default")
      (node (ref "C37") (pin "1") (pinfunction "1_1") (pintype "passive"))
      (node (ref "J1") (pin "1") (pinfunction "Signal_1") (pintype "input"))
      (node (ref "L3") (pin "1") (pinfunction "1_1") (pintype "passive"))
    )
    (net (code "37") (name "V12_out") (class "Default")
      (node (ref "D22") (pin "1") (pinfunction "C_1") (pintype "passive"))
      (node (ref "P1") (pin "7") (pinfunction "7_7") (pintype "passive"))
    )
    (net (code "38") (name "Vout") (class "Default")
      (node (ref "C1") (pin "1") (pinfunction "1_1") (pintype "passive"))
      (node (ref "C3") (pin "1") (pinfunction "1_1") (pintype "passive"))
      (node (ref "D1") (pin "1") (pinfunction "C_1") (pintype "passive"))
      (node (ref "P2") (pin "2") (pinfunction "2_2") (pintype "passive"))
      (node (ref "R1") (pin "2") (pinfunction "2_2") (pintype "passive"))
    )
  )
)
